# M177v2.net
KiCad netlist of a schematic drawn in EAGLE
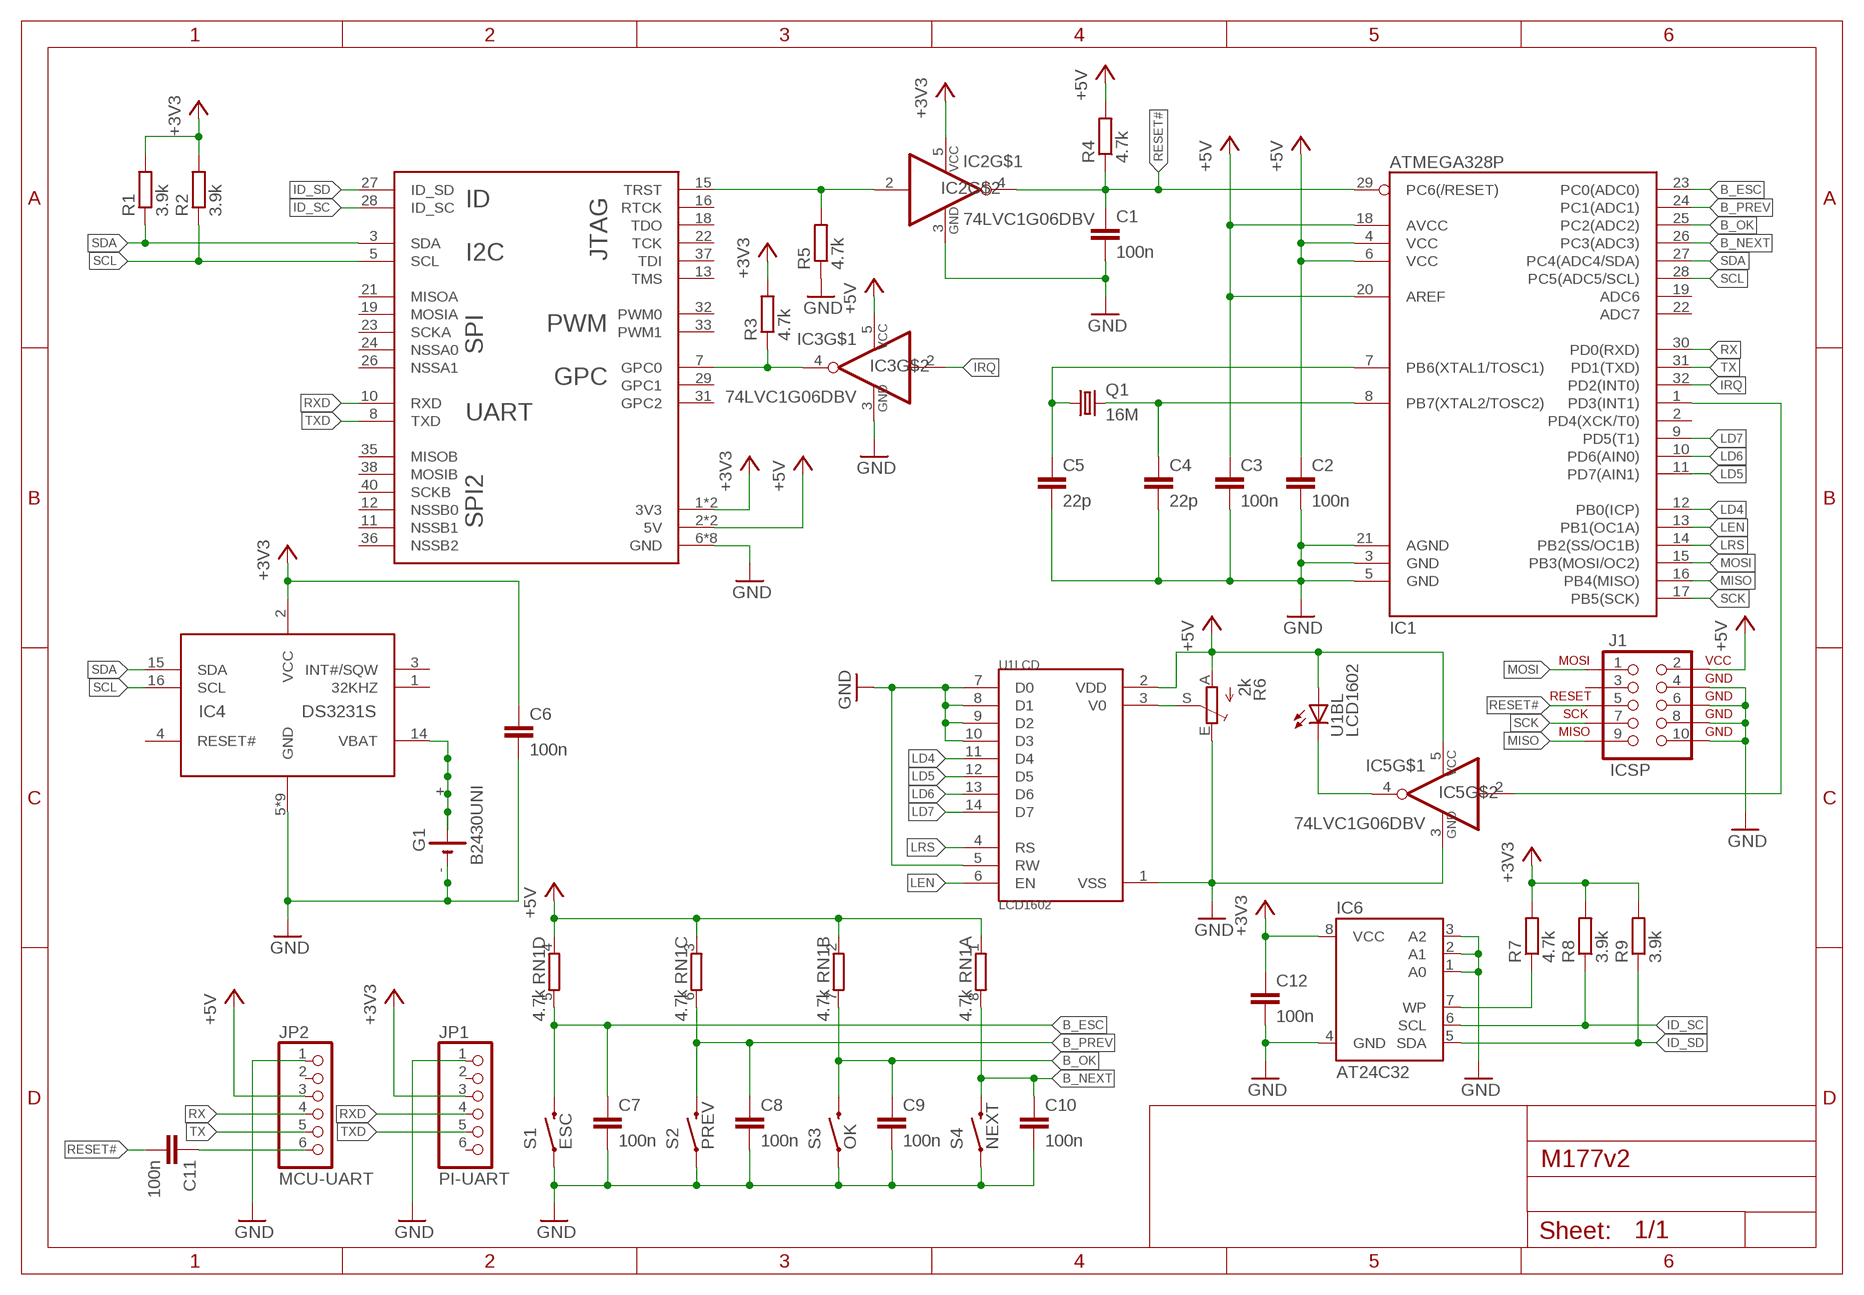
[diagram p0: schematic, sheet 1]

(export (version "E")
  (design (tool "Eeschema 10.0.6"))
  (components
    (comp (ref "C1")
      (value "100n")
      (footprint "eagle-import:C0603")
      (libsource (lib "eagle-import") (part "C-EUC0603"))
    )
    (comp (ref "C2")
      (value "100n")
      (footprint "eagle-import:C0603")
      (libsource (lib "eagle-import") (part "C-EUC0603"))
    )
    (comp (ref "C3")
      (value "100n")
      (footprint "eagle-import:C0603")
      (libsource (lib "eagle-import") (part "C-EUC0603"))
    )
    (comp (ref "C4")
      (value "22p")
      (footprint "eagle-import:C0603")
      (libsource (lib "eagle-import") (part "C-EUC0603"))
    )
    (comp (ref "C5")
      (value "22p")
      (footprint "eagle-import:C0603")
      (libsource (lib "eagle-import") (part "C-EUC0603"))
    )
    (comp (ref "C6")
      (value "100n")
      (footprint "eagle-import:C0603")
      (libsource (lib "eagle-import") (part "C-EUC0603"))
    )
    (comp (ref "C7")
      (value "100n")
      (footprint "eagle-import:C0603")
      (libsource (lib "eagle-import") (part "C-EUC0603"))
    )
    (comp (ref "C8")
      (value "100n")
      (footprint "eagle-import:C0603")
      (libsource (lib "eagle-import") (part "C-EUC0603"))
    )
    (comp (ref "C9")
      (value "100n")
      (footprint "eagle-import:C0603")
      (libsource (lib "eagle-import") (part "C-EUC0603"))
    )
    (comp (ref "C10")
      (value "100n")
      (footprint "eagle-import:C0603")
      (libsource (lib "eagle-import") (part "C-EUC0603"))
    )
    (comp (ref "C11")
      (value "100n")
      (footprint "eagle-import:C0603")
      (libsource (lib "eagle-import") (part "C-EUC0603"))
    )
    (comp (ref "C12")
      (value "100n")
      (footprint "eagle-import:C0603")
      (libsource (lib "eagle-import") (part "C-EUC0603"))
    )
    (comp (ref "G1")
      (value "B2430UNI")
      (footprint "eagle-import:B2430UNI")
      (libsource (lib "eagle-import") (part "B2430UNI"))
    )
    (comp (ref "IC1")
      (value "ATMEGA328P")
      (footprint "eagle-import:TQFP32-08")
      (libsource (lib "eagle-import") (part "ATMEGA328_SMT"))
    )
    (comp (ref "IC2")
      (value "74LVC1G06DBV")
      (footprint "eagle-import:SOT23-5")
      (libsource (lib "eagle-import") (part "741G06DBVLVC"))
    )
    (comp (ref "IC3")
      (value "74LVC1G06DBV")
      (footprint "eagle-import:SOT23-5")
      (libsource (lib "eagle-import") (part "741G06DBVLVC"))
    )
    (comp (ref "IC4")
      (value "DS3231S")
      (footprint "eagle-import:SO16W")
      (libsource (lib "eagle-import") (part "DS3231S"))
    )
    (comp (ref "IC5")
      (value "74LVC1G06DBV")
      (footprint "eagle-import:SOT23-5")
      (libsource (lib "eagle-import") (part "741G06DBVLVC"))
    )
    (comp (ref "IC6")
      (value "AT24C32")
      (footprint "eagle-import:SO-08")
      (libsource (lib "eagle-import") (part "AT24CH"))
    )
    (comp (ref "J1")
      (value "ICSP")
      (footprint "eagle-import:2X5-SHROUDED")
      (libsource (lib "eagle-import") (part "AVR_SPI_PROG2PTH2"))
    )
    (comp (ref "JP1")
      (value "PI-UART")
      (footprint "eagle-import:1X06")
      (libsource (lib "eagle-import") (part "PINHD-1X6"))
    )
    (comp (ref "JP2")
      (value "MCU-UART")
      (footprint "eagle-import:1X06")
      (libsource (lib "eagle-import") (part "PINHD-1X6"))
    )
    (comp (ref "Q1")
      (value "16M")
      (footprint "eagle-import:HC49_S")
      (libsource (lib "eagle-import") (part "CRYSTALHC49S"))
    )
    (comp (ref "R1")
      (value "3.9k")
      (footprint "eagle-import:R0603")
      (libsource (lib "eagle-import") (part "R-EU_R0603"))
    )
    (comp (ref "R2")
      (value "3.9k")
      (footprint "eagle-import:R0603")
      (libsource (lib "eagle-import") (part "R-EU_R0603"))
    )
    (comp (ref "R3")
      (value "4.7k")
      (footprint "eagle-import:R0603")
      (libsource (lib "eagle-import") (part "R-EU_R0603"))
    )
    (comp (ref "R4")
      (value "4.7k")
      (footprint "eagle-import:R0603")
      (libsource (lib "eagle-import") (part "R-EU_R0603"))
    )
    (comp (ref "R5")
      (value "4.7k")
      (footprint "eagle-import:R0603")
      (libsource (lib "eagle-import") (part "R-EU_R0603"))
    )
    (comp (ref "R6")
      (value "2k")
      (footprint "eagle-import:CA6V")
      (libsource (lib "eagle-import") (part "TRIM_EU-CA6V"))
    )
    (comp (ref "R7")
      (value "4.7k")
      (footprint "eagle-import:R0603")
      (libsource (lib "eagle-import") (part "R-EU_R0603"))
    )
    (comp (ref "R8")
      (value "3.9k")
      (footprint "eagle-import:R0603")
      (libsource (lib "eagle-import") (part "R-EU_R0603"))
    )
    (comp (ref "R9")
      (value "3.9k")
      (footprint "eagle-import:R0603")
      (libsource (lib "eagle-import") (part "R-EU_R0603"))
    )
    (comp (ref "RN1")
      (value "4.7k")
      (footprint "eagle-import:0603-ARV")
      (libsource (lib "eagle-import") (part "4R-N0603-ARV"))
    )
    (comp (ref "S1")
      (value "ESC")
      (footprint "eagle-import:TACTILE-SWITCH-1101NE")
      (libsource (lib "eagle-import") (part "SWITCH-MOMENTARY-2-SMD-1101NE"))
    )
    (comp (ref "S2")
      (value "PREV")
      (footprint "eagle-import:TACTILE-SWITCH-1101NE")
      (libsource (lib "eagle-import") (part "SWITCH-MOMENTARY-2-SMD-1101NE"))
    )
    (comp (ref "S3")
      (value "OK")
      (footprint "eagle-import:TACTILE-SWITCH-1101NE")
      (libsource (lib "eagle-import") (part "SWITCH-MOMENTARY-2-SMD-1101NE"))
    )
    (comp (ref "S4")
      (value "NEXT")
      (footprint "eagle-import:TACTILE-SWITCH-1101NE")
      (libsource (lib "eagle-import") (part "SWITCH-MOMENTARY-2-SMD-1101NE"))
    )
    (comp (ref "U1")
      (value "LCD1602")
      (footprint "eagle-import:LCD1602A")
      (libsource (lib "eagle-import") (part "LCD1602"))
    )
    (comp (ref "U2")
      (value "RASPI-B+H")
      (footprint "eagle-import:HAT")
      (libsource (lib "eagle-import") (part "RASPI-B+H"))
    )
  )
  (nets
    (net (code "1") (name "+3V3") (class "Default")
      (node (ref "C12") (pin "1") (pinfunction "1_1") (pintype "passive"))
      (node (ref "C6") (pin "1") (pinfunction "1_1") (pintype "passive"))
      (node (ref "IC2") (pin "5") (pinfunction "VCC_5") (pintype "power_in"))
      (node (ref "IC4") (pin "2") (pinfunction "VCC_2") (pintype "power_in"))
      (node (ref "IC6") (pin "8") (pinfunction "VCC_8") (pintype "power_in"))
      (node (ref "JP1") (pin "3") (pinfunction "3_3") (pintype "passive"))
      (node (ref "R1") (pin "2") (pinfunction "2_2") (pintype "passive"))
      (node (ref "R2") (pin "2") (pinfunction "2_2") (pintype "passive"))
      (node (ref "R3") (pin "2") (pinfunction "2_2") (pintype "passive"))
      (node (ref "R7") (pin "2") (pinfunction "2_2") (pintype "passive"))
      (node (ref "R8") (pin "2") (pinfunction "2_2") (pintype "passive"))
      (node (ref "R9") (pin "2") (pinfunction "2_2") (pintype "passive"))
      (node (ref "U2") (pin "1") (pinfunction "3V3_1") (pintype "power_in"))
      (node (ref "U2") (pin "17") (pinfunction "3V3_17") (pintype "power_in"))
    )
    (net (code "2") (name "+5V") (class "Default")
      (node (ref "C2") (pin "1") (pinfunction "1_1") (pintype "passive"))
      (node (ref "C3") (pin "1") (pinfunction "1_1") (pintype "passive"))
      (node (ref "IC1") (pin "18") (pinfunction "AVCC_18") (pintype "bidirectional"))
      (node (ref "IC1") (pin "20") (pinfunction "AREF_20") (pintype "bidirectional"))
      (node (ref "IC1") (pin "4") (pinfunction "VCC_4") (pintype "bidirectional"))
      (node (ref "IC1") (pin "6") (pinfunction "VCC_6") (pintype "bidirectional"))
      (node (ref "IC3") (pin "5") (pinfunction "VCC_5") (pintype "power_in"))
      (node (ref "IC5") (pin "5") (pinfunction "VCC_5") (pintype "power_in"))
      (node (ref "J1") (pin "2") (pinfunction "VCC_2") (pintype "power_in"))
      (node (ref "JP2") (pin "3") (pinfunction "3_3") (pintype "passive"))
      (node (ref "R4") (pin "2") (pinfunction "2_2") (pintype "passive"))
      (node (ref "R6") (pin "A") (pinfunction "A_A") (pintype "passive"))
      (node (ref "RN1") (pin "1") (pinfunction "1_1") (pintype "passive"))
      (node (ref "RN1") (pin "2") (pinfunction "1_2") (pintype "passive"))
      (node (ref "RN1") (pin "3") (pinfunction "1_3") (pintype "passive"))
      (node (ref "RN1") (pin "4") (pinfunction "1_4") (pintype "passive"))
      (node (ref "U1") (pin "15") (pinfunction "A_15") (pintype "passive"))
      (node (ref "U1") (pin "2") (pinfunction "VDD_2") (pintype "power_in"))
      (node (ref "U2") (pin "2") (pinfunction "5V_2") (pintype "power_in"))
      (node (ref "U2") (pin "4") (pinfunction "5V_4") (pintype "power_in"))
    )
    (net (code "3") (name "B_ESC") (class "Default")
      (node (ref "C7") (pin "1") (pinfunction "1_1") (pintype "passive"))
      (node (ref "IC1") (pin "23") (pinfunction "PC0(ADC0)_23") (pintype "bidirectional"))
      (node (ref "RN1") (pin "5") (pinfunction "2_5") (pintype "passive"))
      (node (ref "S1") (pin "2") (pinfunction "2_2") (pintype "passive"))
    )
    (net (code "4") (name "B_NEXT") (class "Default")
      (node (ref "C10") (pin "1") (pinfunction "1_1") (pintype "passive"))
      (node (ref "IC1") (pin "26") (pinfunction "PC3(ADC3)_26") (pintype "bidirectional"))
      (node (ref "RN1") (pin "8") (pinfunction "2_8") (pintype "passive"))
      (node (ref "S4") (pin "2") (pinfunction "2_2") (pintype "passive"))
    )
    (net (code "5") (name "B_OK") (class "Default")
      (node (ref "C9") (pin "1") (pinfunction "1_1") (pintype "passive"))
      (node (ref "IC1") (pin "25") (pinfunction "PC2(ADC2)_25") (pintype "bidirectional"))
      (node (ref "RN1") (pin "7") (pinfunction "2_7") (pintype "passive"))
      (node (ref "S3") (pin "2") (pinfunction "2_2") (pintype "passive"))
    )
    (net (code "6") (name "B_PREV") (class "Default")
      (node (ref "C8") (pin "1") (pinfunction "1_1") (pintype "passive"))
      (node (ref "IC1") (pin "24") (pinfunction "PC1(ADC1)_24") (pintype "bidirectional"))
      (node (ref "RN1") (pin "6") (pinfunction "2_6") (pintype "passive"))
      (node (ref "S2") (pin "2") (pinfunction "2_2") (pintype "passive"))
    )
    (net (code "7") (name "GND") (class "Default")
      (node (ref "C1") (pin "2") (pinfunction "2_2") (pintype "passive"))
      (node (ref "C10") (pin "2") (pinfunction "2_2") (pintype "passive"))
      (node (ref "C12") (pin "2") (pinfunction "2_2") (pintype "passive"))
      (node (ref "C2") (pin "2") (pinfunction "2_2") (pintype "passive"))
      (node (ref "C3") (pin "2") (pinfunction "2_2") (pintype "passive"))
      (node (ref "C4") (pin "2") (pinfunction "2_2") (pintype "passive"))
      (node (ref "C5") (pin "2") (pinfunction "2_2") (pintype "passive"))
      (node (ref "C6") (pin "2") (pinfunction "2_2") (pintype "passive"))
      (node (ref "C7") (pin "2") (pinfunction "2_2") (pintype "passive"))
      (node (ref "C8") (pin "2") (pinfunction "2_2") (pintype "passive"))
      (node (ref "C9") (pin "2") (pinfunction "2_2") (pintype "passive"))
      (node (ref "G1") (pin "-") (pinfunction "-_-") (pintype "passive"))
      (node (ref "G1") (pin "-@1") (pinfunction "-_-@1") (pintype "passive"))
      (node (ref "IC1") (pin "21") (pinfunction "AGND_21") (pintype "bidirectional"))
      (node (ref "IC1") (pin "3") (pinfunction "GND_3") (pintype "bidirectional"))
      (node (ref "IC1") (pin "5") (pinfunction "GND_5") (pintype "bidirectional"))
      (node (ref "IC2") (pin "3") (pinfunction "GND_3") (pintype "power_in"))
      (node (ref "IC3") (pin "3") (pinfunction "GND_3") (pintype "power_in"))
      (node (ref "IC4") (pin "10") (pinfunction "GND_10") (pintype "power_in"))
      (node (ref "IC4") (pin "11") (pinfunction "GND_11") (pintype "power_in"))
      (node (ref "IC4") (pin "12") (pinfunction "GND_12") (pintype "power_in"))
      (node (ref "IC4") (pin "13") (pinfunction "GND_13") (pintype "power_in"))
      (node (ref "IC4") (pin "5") (pinfunction "GND_5") (pintype "power_in"))
      (node (ref "IC4") (pin "6") (pinfunction "GND_6") (pintype "power_in"))
      (node (ref "IC4") (pin "7") (pinfunction "GND_7") (pintype "power_in"))
      (node (ref "IC4") (pin "8") (pinfunction "GND_8") (pintype "power_in"))
      (node (ref "IC4") (pin "9") (pinfunction "GND_9") (pintype "power_in"))
      (node (ref "IC5") (pin "3") (pinfunction "GND_3") (pintype "power_in"))
      (node (ref "IC6") (pin "1") (pinfunction "A0_1") (pintype "input"))
      (node (ref "IC6") (pin "2") (pinfunction "A1_2") (pintype "input"))
      (node (ref "IC6") (pin "3") (pinfunction "A2_3") (pintype "input"))
      (node (ref "IC6") (pin "4") (pinfunction "GND_4") (pintype "power_in"))
      (node (ref "J1") (pin "10") (pinfunction "GND_10") (pintype "power_in"))
      (node (ref "J1") (pin "4") (pinfunction "GND_4") (pintype "power_in"))
      (node (ref "J1") (pin "6") (pinfunction "GND_6") (pintype "power_in"))
      (node (ref "J1") (pin "8") (pinfunction "GND_8") (pintype "power_in"))
      (node (ref "JP1") (pin "1") (pinfunction "1_1") (pintype "passive"))
      (node (ref "JP2") (pin "1") (pinfunction "1_1") (pintype "passive"))
      (node (ref "R5") (pin "1") (pinfunction "1_1") (pintype "passive"))
      (node (ref "R6") (pin "E") (pinfunction "E_E") (pintype "passive"))
      (node (ref "S1") (pin "1") (pinfunction "1_1") (pintype "passive"))
      (node (ref "S2") (pin "1") (pinfunction "1_1") (pintype "passive"))
      (node (ref "S3") (pin "1") (pinfunction "1_1") (pintype "passive"))
      (node (ref "S4") (pin "1") (pinfunction "1_1") (pintype "passive"))
      (node (ref "U1") (pin "1") (pinfunction "VSS_1") (pintype "power_in"))
      (node (ref "U1") (pin "10") (pinfunction "D3_10") (pintype "input"))
      (node (ref "U1") (pin "5") (pinfunction "RW_5") (pintype "input"))
      (node (ref "U1") (pin "7") (pinfunction "D0_7") (pintype "input"))
      (node (ref "U1") (pin "8") (pinfunction "D1_8") (pintype "input"))
      (node (ref "U1") (pin "9") (pinfunction "D2_9") (pintype "input"))
      (node (ref "U2") (pin "14") (pinfunction "GND_14") (pintype "power_in"))
      (node (ref "U2") (pin "20") (pinfunction "GND_20") (pintype "power_in"))
      (node (ref "U2") (pin "25") (pinfunction "GND_25") (pintype "power_in"))
      (node (ref "U2") (pin "30") (pinfunction "GND_30") (pintype "power_in"))
      (node (ref "U2") (pin "34") (pinfunction "GND_34") (pintype "power_in"))
      (node (ref "U2") (pin "39") (pinfunction "GND_39") (pintype "power_in"))
      (node (ref "U2") (pin "6") (pinfunction "GND_6") (pintype "power_in"))
      (node (ref "U2") (pin "9") (pinfunction "GND_9") (pintype "power_in"))
    )
    (net (code "8") (name "ID_SC") (class "Default")
      (node (ref "IC6") (pin "6") (pinfunction "SCL_6") (pintype "bidirectional"))
      (node (ref "R8") (pin "1") (pinfunction "1_1") (pintype "passive"))
      (node (ref "U2") (pin "28") (pinfunction "ID_SC_28") (pintype "bidirectional"))
    )
    (net (code "9") (name "ID_SD") (class "Default")
      (node (ref "IC6") (pin "5") (pinfunction "SDA_5") (pintype "bidirectional"))
      (node (ref "R9") (pin "1") (pinfunction "1_1") (pintype "passive"))
      (node (ref "U2") (pin "27") (pinfunction "ID_SD_27") (pintype "bidirectional"))
    )
    (net (code "10") (name "IRQ") (class "Default")
      (node (ref "IC1") (pin "32") (pinfunction "PD2(INT0)_32") (pintype "bidirectional"))
      (node (ref "IC3") (pin "2") (pinfunction "I_2") (pintype "input"))
    )
    (net (code "11") (name "LD4") (class "Default")
      (node (ref "IC1") (pin "12") (pinfunction "PB0(ICP)_12") (pintype "bidirectional"))
      (node (ref "U1") (pin "11") (pinfunction "D4_11") (pintype "input"))
    )
    (net (code "12") (name "LD5") (class "Default")
      (node (ref "IC1") (pin "11") (pinfunction "PD7(AIN1)_11") (pintype "bidirectional"))
      (node (ref "U1") (pin "12") (pinfunction "D5_12") (pintype "input"))
    )
    (net (code "13") (name "LD6") (class "Default")
      (node (ref "IC1") (pin "10") (pinfunction "PD6(AIN0)_10") (pintype "bidirectional"))
      (node (ref "U1") (pin "13") (pinfunction "D6_13") (pintype "input"))
    )
    (net (code "14") (name "LD7") (class "Default")
      (node (ref "IC1") (pin "9") (pinfunction "PD5(T1)_9") (pintype "bidirectional"))
      (node (ref "U1") (pin "14") (pinfunction "D7_14") (pintype "input"))
    )
    (net (code "15") (name "LEN") (class "Default")
      (node (ref "IC1") (pin "13") (pinfunction "PB1(OC1A)_13") (pintype "bidirectional"))
      (node (ref "U1") (pin "6") (pinfunction "EN_6") (pintype "input"))
    )
    (net (code "16") (name "LRS") (class "Default")
      (node (ref "IC1") (pin "14") (pinfunction "PB2(SS/OC1B)_14") (pintype "bidirectional"))
      (node (ref "U1") (pin "4") (pinfunction "RS_4") (pintype "input"))
    )
    (net (code "17") (name "MISO") (class "Default")
      (node (ref "IC1") (pin "16") (pinfunction "PB4(MISO)_16") (pintype "bidirectional"))
      (node (ref "J1") (pin "9") (pinfunction "MISO_9") (pintype "passive"))
    )
    (net (code "18") (name "MOSI") (class "Default")
      (node (ref "IC1") (pin "15") (pinfunction "PB3(MOSI/OC2)_15") (pintype "bidirectional"))
      (node (ref "J1") (pin "1") (pinfunction "MOSI_1") (pintype "passive"))
    )
    (net (code "19") (name "Net-(C11-Pad1)") (class "Default")
      (node (ref "C11") (pin "1") (pinfunction "1_1") (pintype "passive"))
      (node (ref "JP2") (pin "6") (pinfunction "6_6") (pintype "passive"))
    )
    (net (code "20") (name "Net-(IC1-PB6(XTAL1{slash}TOSC1))") (class "Default")
      (node (ref "C5") (pin "1") (pinfunction "1_1") (pintype "passive"))
      (node (ref "IC1") (pin "7") (pinfunction "PB6(XTAL1/TOSC1)_7") (pintype "bidirectional"))
      (node (ref "Q1") (pin "1") (pinfunction "1_1") (pintype "passive"))
    )
    (net (code "21") (name "Net-(IC1-PB7(XTAL2{slash}TOSC2))") (class "Default")
      (node (ref "C4") (pin "1") (pinfunction "1_1") (pintype "passive"))
      (node (ref "IC1") (pin "8") (pinfunction "PB7(XTAL2/TOSC2)_8") (pintype "bidirectional"))
      (node (ref "Q1") (pin "2") (pinfunction "2_2") (pintype "passive"))
    )
    (net (code "22") (name "Net-(IC1-PD3(INT1))") (class "Default")
      (node (ref "IC1") (pin "1") (pinfunction "PD3(INT1)_1") (pintype "bidirectional"))
      (node (ref "IC5") (pin "2") (pinfunction "I_2") (pintype "input"))
    )
    (net (code "23") (name "Net-(IC2A-I)") (class "Default")
      (node (ref "IC2") (pin "2") (pinfunction "I_2") (pintype "input"))
      (node (ref "R5") (pin "2") (pinfunction "2_2") (pintype "passive"))
      (node (ref "U2") (pin "15") (pinfunction "TRST_15") (pintype "bidirectional"))
    )
    (net (code "24") (name "Net-(IC3A-O)") (class "Default")
      (node (ref "IC3") (pin "4") (pinfunction "O_4") (pintype "open_collector"))
      (node (ref "R3") (pin "1") (pinfunction "1_1") (pintype "passive"))
      (node (ref "U2") (pin "7") (pinfunction "GPC0_7") (pintype "bidirectional"))
    )
    (net (code "25") (name "Net-(IC4-VBAT)") (class "Default")
      (node (ref "G1") (pin "+") (pinfunction "+_+") (pintype "passive"))
      (node (ref "G1") (pin "+@1") (pinfunction "+_+@1") (pintype "passive"))
      (node (ref "G1") (pin "+@2") (pinfunction "+_+@2") (pintype "passive"))
      (node (ref "G1") (pin "+@3") (pinfunction "+_+@3") (pintype "passive"))
      (node (ref "G1") (pin "+@4") (pinfunction "+_+@4") (pintype "passive"))
      (node (ref "IC4") (pin "14") (pinfunction "VBAT_14") (pintype "power_in"))
    )
    (net (code "26") (name "Net-(IC5A-O)") (class "Default")
      (node (ref "IC5") (pin "4") (pinfunction "O_4") (pintype "open_collector"))
      (node (ref "U1") (pin "16") (pinfunction "C_16") (pintype "passive"))
    )
    (net (code "27") (name "Net-(IC6-WP)") (class "Default")
      (node (ref "IC6") (pin "7") (pinfunction "WP_7") (pintype "input"))
      (node (ref "R7") (pin "1") (pinfunction "1_1") (pintype "passive"))
    )
    (net (code "28") (name "Net-(U1B-V0)") (class "Default")
      (node (ref "R6") (pin "S") (pinfunction "S_S") (pintype "passive"))
      (node (ref "U1") (pin "3") (pinfunction "V0_3") (pintype "passive"))
    )
    (net (code "29") (name "RESET#") (class "Default")
      (node (ref "C1") (pin "1") (pinfunction "1_1") (pintype "passive"))
      (node (ref "C11") (pin "2") (pinfunction "2_2") (pintype "passive"))
      (node (ref "IC1") (pin "29") (pinfunction "PC6(/RESET)_29") (pintype "bidirectional"))
      (node (ref "IC2") (pin "4") (pinfunction "O_4") (pintype "open_collector"))
      (node (ref "J1") (pin "5") (pinfunction "RESET_5") (pintype "passive"))
      (node (ref "R4") (pin "1") (pinfunction "1_1") (pintype "passive"))
    )
    (net (code "30") (name "RX") (class "Default")
      (node (ref "IC1") (pin "30") (pinfunction "PD0(RXD)_30") (pintype "bidirectional"))
      (node (ref "JP2") (pin "4") (pinfunction "4_4") (pintype "passive"))
    )
    (net (code "31") (name "RXD") (class "Default")
      (node (ref "JP1") (pin "4") (pinfunction "4_4") (pintype "passive"))
      (node (ref "U2") (pin "10") (pinfunction "RXD_10") (pintype "bidirectional"))
    )
    (net (code "32") (name "SCK") (class "Default")
      (node (ref "IC1") (pin "17") (pinfunction "PB5(SCK)_17") (pintype "bidirectional"))
      (node (ref "J1") (pin "7") (pinfunction "SCK_7") (pintype "passive"))
    )
    (net (code "33") (name "SCL") (class "Default")
      (node (ref "IC1") (pin "28") (pinfunction "PC5(ADC5/SCL)_28") (pintype "bidirectional"))
      (node (ref "IC4") (pin "16") (pinfunction "SCL_16") (pintype "bidirectional"))
      (node (ref "R2") (pin "1") (pinfunction "1_1") (pintype "passive"))
      (node (ref "U2") (pin "5") (pinfunction "SCL_5") (pintype "bidirectional"))
    )
    (net (code "34") (name "SDA") (class "Default")
      (node (ref "IC1") (pin "27") (pinfunction "PC4(ADC4/SDA)_27") (pintype "bidirectional"))
      (node (ref "IC4") (pin "15") (pinfunction "SDA_15") (pintype "bidirectional"))
      (node (ref "R1") (pin "1") (pinfunction "1_1") (pintype "passive"))
      (node (ref "U2") (pin "3") (pinfunction "SDA_3") (pintype "bidirectional"))
    )
    (net (code "35") (name "TX") (class "Default")
      (node (ref "IC1") (pin "31") (pinfunction "PD1(TXD)_31") (pintype "bidirectional"))
      (node (ref "JP2") (pin "5") (pinfunction "5_5") (pintype "passive"))
    )
    (net (code "36") (name "TXD") (class "Default")
      (node (ref "JP1") (pin "5") (pinfunction "5_5") (pintype "passive"))
      (node (ref "U2") (pin "8") (pinfunction "TXD_8") (pintype "bidirectional"))
    )
    (net (code "37") (name "unconnected-(IC1-ADC6-Pad19)") (class "Default")
      (node (ref "IC1") (pin "19") (pinfunction "ADC6_19") (pintype "bidirectional"))
    )
    (net (code "38") (name "unconnected-(IC1-ADC7-Pad22)") (class "Default")
      (node (ref "IC1") (pin "22") (pinfunction "ADC7_22") (pintype "bidirectional"))
    )
    (net (code "39") (name "unconnected-(IC1-PD4(XCK{slash}T0)-Pad2)") (class "Default")
      (node (ref "IC1") (pin "2") (pinfunction "PD4(XCK/T0)_2") (pintype "bidirectional"))
    )
    (net (code "40") (name "unconnected-(IC4-32KHZ-Pad1)") (class "Default")
      (node (ref "IC4") (pin "1") (pinfunction "32KHZ_1") (pintype "output"))
    )
    (net (code "41") (name "unconnected-(IC4-INT#{slash}SQW-Pad3)") (class "Default")
      (node (ref "IC4") (pin "3") (pinfunction "INT#/SQW_3") (pintype "output"))
    )
    (net (code "42") (name "unconnected-(IC4-RESET#-Pad4)") (class "Default")
      (node (ref "IC4") (pin "4") (pinfunction "RESET#_4") (pintype "input"))
    )
    (net (code "43") (name "unconnected-(J1-NC-Pad3)") (class "Default")
      (node (ref "J1") (pin "3") (pinfunction "NC_3") (pintype "no_connect"))
    )
    (net (code "44") (name "unconnected-(JP1-Pad2)") (class "Default")
      (node (ref "JP1") (pin "2") (pinfunction "2_2") (pintype "passive"))
    )
    (net (code "45") (name "unconnected-(JP1-Pad6)") (class "Default")
      (node (ref "JP1") (pin "6") (pinfunction "6_6") (pintype "passive"))
    )
    (net (code "46") (name "unconnected-(JP2-Pad2)") (class "Default")
      (node (ref "JP2") (pin "2") (pinfunction "2_2") (pintype "passive"))
    )
    (net (code "47") (name "unconnected-(U2-GPC1-Pad29)") (class "Default")
      (node (ref "U2") (pin "29") (pinfunction "GPC1_29") (pintype "bidirectional"))
    )
    (net (code "48") (name "unconnected-(U2-GPC2-Pad31)") (class "Default")
      (node (ref "U2") (pin "31") (pinfunction "GPC2_31") (pintype "bidirectional"))
    )
    (net (code "49") (name "unconnected-(U2-MISOA-Pad21)") (class "Default")
      (node (ref "U2") (pin "21") (pinfunction "MISOA_21") (pintype "bidirectional"))
    )
    (net (code "50") (name "unconnected-(U2-MISOB-Pad35)") (class "Default")
      (node (ref "U2") (pin "35") (pinfunction "MISOB_35") (pintype "bidirectional"))
    )
    (net (code "51") (name "unconnected-(U2-MOSIA-Pad19)") (class "Default")
      (node (ref "U2") (pin "19") (pinfunction "MOSIA_19") (pintype "bidirectional"))
    )
    (net (code "52") (name "unconnected-(U2-MOSIB-Pad38)") (class "Default")
      (node (ref "U2") (pin "38") (pinfunction "MOSIB_38") (pintype "bidirectional"))
    )
    (net (code "53") (name "unconnected-(U2-NSSA0-Pad24)") (class "Default")
      (node (ref "U2") (pin "24") (pinfunction "NSSA0_24") (pintype "bidirectional"))
    )
    (net (code "54") (name "unconnected-(U2-NSSA1-Pad26)") (class "Default")
      (node (ref "U2") (pin "26") (pinfunction "NSSA1_26") (pintype "bidirectional"))
    )
    (net (code "55") (name "unconnected-(U2-NSSB0-Pad12)") (class "Default")
      (node (ref "U2") (pin "12") (pinfunction "NSSB0_12") (pintype "bidirectional"))
    )
    (net (code "56") (name "unconnected-(U2-NSSB1-Pad11)") (class "Default")
      (node (ref "U2") (pin "11") (pinfunction "NSSB1_11") (pintype "bidirectional"))
    )
    (net (code "57") (name "unconnected-(U2-NSSB2-Pad36)") (class "Default")
      (node (ref "U2") (pin "36") (pinfunction "NSSB2_36") (pintype "bidirectional"))
    )
    (net (code "58") (name "unconnected-(U2-PWM0-Pad32)") (class "Default")
      (node (ref "U2") (pin "32") (pinfunction "PWM0_32") (pintype "bidirectional"))
    )
    (net (code "59") (name "unconnected-(U2-PWM1-Pad33)") (class "Default")
      (node (ref "U2") (pin "33") (pinfunction "PWM1_33") (pintype "bidirectional"))
    )
    (net (code "60") (name "unconnected-(U2-RTCK-Pad16)") (class "Default")
      (node (ref "U2") (pin "16") (pinfunction "RTCK_16") (pintype "bidirectional"))
    )
    (net (code "61") (name "unconnected-(U2-SCKA-Pad23)") (class "Default")
      (node (ref "U2") (pin "23") (pinfunction "SCKA_23") (pintype "bidirectional"))
    )
    (net (code "62") (name "unconnected-(U2-SCKB-Pad40)") (class "Default")
      (node (ref "U2") (pin "40") (pinfunction "SCKB_40") (pintype "bidirectional"))
    )
    (net (code "63") (name "unconnected-(U2-TCK-Pad22)") (class "Default")
      (node (ref "U2") (pin "22") (pinfunction "TCK_22") (pintype "bidirectional"))
    )
    (net (code "64") (name "unconnected-(U2-TDI-Pad37)") (class "Default")
      (node (ref "U2") (pin "37") (pinfunction "TDI_37") (pintype "bidirectional"))
    )
    (net (code "65") (name "unconnected-(U2-TDO-Pad18)") (class "Default")
      (node (ref "U2") (pin "18") (pinfunction "TDO_18") (pintype "bidirectional"))
    )
    (net (code "66") (name "unconnected-(U2-TMS-Pad13)") (class "Default")
      (node (ref "U2") (pin "13") (pinfunction "TMS_13") (pintype "bidirectional"))
    )
  )
)
